# Ex_Controller_ExPwr.net
KiCad netlist of a schematic drawn in EAGLE
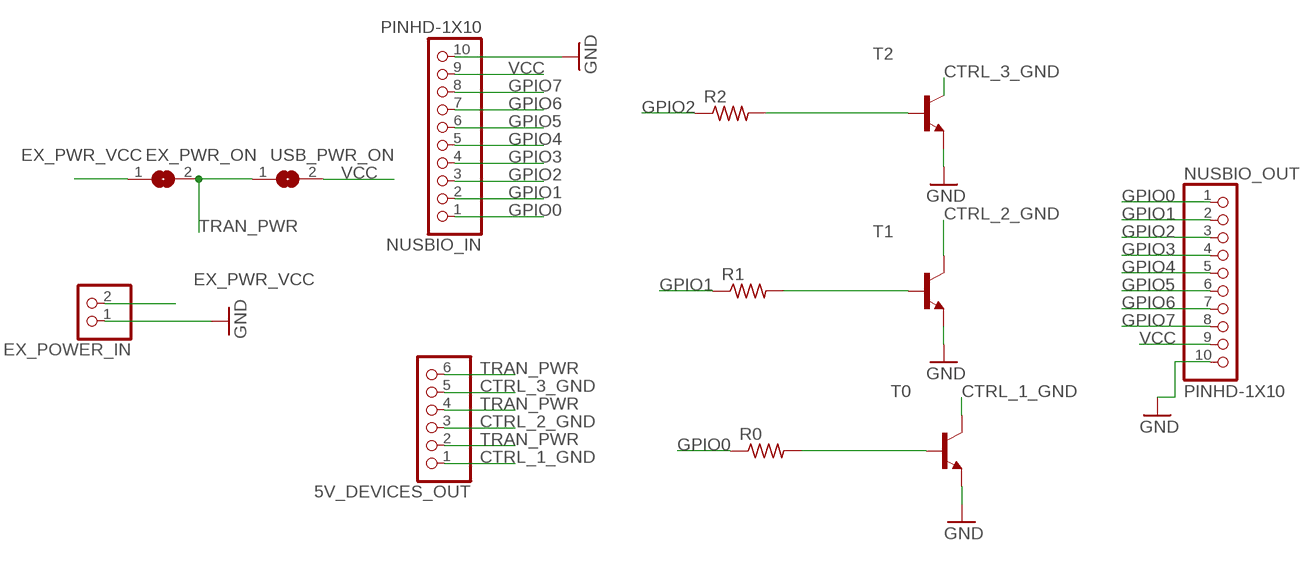
[diagram p0: schematic, sheet 1]

(export (version "E")
  (design (tool "Eeschema 10.0.6"))
  (components
    (comp (ref "5V_DEVICES_OUT")
      (value "PINHD-1X6")
      (footprint "eagle-import:1X06")
      (libsource (lib "eagle-import") (part "PINHD-1X6"))
    )
    (comp (ref "EX_POWER_IN")
      (value "PINHD-1X2")
      (footprint "eagle-import:1X02")
      (libsource (lib "eagle-import") (part "PINHD-1X2"))
    )
    (comp (ref "EX_PWR_ON")
      (value "SOLDERJUMPERREFLOW")
      (footprint "eagle-import:SOLDERJUMPER_REFLOW")
      (libsource (lib "eagle-import") (part "SOLDERJUMPERREFLOW"))
    )
    (comp (ref "NUSBIO_IN")
      (value "PINHD-1X10")
      (footprint "eagle-import:1X10-BIG")
      (libsource (lib "eagle-import") (part "PINHD-1X10"))
    )
    (comp (ref "NUSBIO_OUT")
      (value "PINHD-1X10")
      (footprint "eagle-import:1X10-BIG")
      (libsource (lib "eagle-import") (part "PINHD-1X10"))
    )
    (comp (ref "R0")
      (value "R-US_R0805")
      (footprint "eagle-import:R0805")
      (libsource (lib "eagle-import") (part "R-US_R0805"))
    )
    (comp (ref "R1")
      (value "R-US_R0805")
      (footprint "eagle-import:R0805")
      (libsource (lib "eagle-import") (part "R-US_R0805"))
    )
    (comp (ref "R2")
      (value "R-US_R0805")
      (footprint "eagle-import:R0805")
      (libsource (lib "eagle-import") (part "R-US_R0805"))
    )
    (comp (ref "T0")
      (value "MMBT3904LT1-NPN-SOT23-BEC")
      (footprint "eagle-import:SOT23-BEC")
      (libsource (lib "eagle-import") (part "-NPN-SOT23-BECMMBT3904LT1"))
    )
    (comp (ref "T1")
      (value "MMBT3904LT1-NPN-SOT23-BEC")
      (footprint "eagle-import:SOT23-BEC")
      (libsource (lib "eagle-import") (part "-NPN-SOT23-BECMMBT3904LT1"))
    )
    (comp (ref "T2")
      (value "MMBT3904LT1-NPN-SOT23-BEC")
      (footprint "eagle-import:SOT23-BEC")
      (libsource (lib "eagle-import") (part "-NPN-SOT23-BECMMBT3904LT1"))
    )
    (comp (ref "USB_PWR_ON")
      (value "SOLDERJUMPERREFLOW")
      (footprint "eagle-import:SOLDERJUMPER_REFLOW")
      (libsource (lib "eagle-import") (part "SOLDERJUMPERREFLOW"))
    )
  )
  (nets
    (net (code "1") (name "/CTRL_1_GND") (class "Default")
      (node (ref "5V_DEVICES_OUT") (pin "1") (pinfunction "1_1") (pintype "passive"))
      (node (ref "T0") (pin "C") (pinfunction "C_C") (pintype "passive"))
    )
    (net (code "2") (name "/CTRL_2_GND") (class "Default")
      (node (ref "5V_DEVICES_OUT") (pin "3") (pinfunction "3_3") (pintype "passive"))
      (node (ref "T1") (pin "C") (pinfunction "C_C") (pintype "passive"))
    )
    (net (code "3") (name "/CTRL_3_GND") (class "Default")
      (node (ref "5V_DEVICES_OUT") (pin "5") (pinfunction "5_5") (pintype "passive"))
      (node (ref "T2") (pin "C") (pinfunction "C_C") (pintype "passive"))
    )
    (net (code "4") (name "/EX_PWR_VCC") (class "Default")
      (node (ref "EX_POWER_IN") (pin "2") (pinfunction "2_2") (pintype "passive"))
      (node (ref "EX_PWR_ON") (pin "1") (pinfunction "1_1") (pintype "passive"))
    )
    (net (code "5") (name "/GPIO0") (class "Default")
      (node (ref "NUSBIO_IN") (pin "1") (pinfunction "1_1") (pintype "passive"))
      (node (ref "NUSBIO_OUT") (pin "1") (pinfunction "1_1") (pintype "passive"))
      (node (ref "R0") (pin "1") (pinfunction "1_1") (pintype "passive"))
    )
    (net (code "6") (name "/GPIO1") (class "Default")
      (node (ref "NUSBIO_IN") (pin "2") (pinfunction "2_2") (pintype "passive"))
      (node (ref "NUSBIO_OUT") (pin "2") (pinfunction "2_2") (pintype "passive"))
      (node (ref "R1") (pin "1") (pinfunction "1_1") (pintype "passive"))
    )
    (net (code "7") (name "/GPIO2") (class "Default")
      (node (ref "NUSBIO_IN") (pin "3") (pinfunction "3_3") (pintype "passive"))
      (node (ref "NUSBIO_OUT") (pin "3") (pinfunction "3_3") (pintype "passive"))
      (node (ref "R2") (pin "1") (pinfunction "1_1") (pintype "passive"))
    )
    (net (code "8") (name "/GPIO3") (class "Default")
      (node (ref "NUSBIO_IN") (pin "4") (pinfunction "4_4") (pintype "passive"))
      (node (ref "NUSBIO_OUT") (pin "4") (pinfunction "4_4") (pintype "passive"))
    )
    (net (code "9") (name "/GPIO4") (class "Default")
      (node (ref "NUSBIO_IN") (pin "5") (pinfunction "5_5") (pintype "passive"))
      (node (ref "NUSBIO_OUT") (pin "5") (pinfunction "5_5") (pintype "passive"))
    )
    (net (code "10") (name "/GPIO5") (class "Default")
      (node (ref "NUSBIO_IN") (pin "6") (pinfunction "6_6") (pintype "passive"))
      (node (ref "NUSBIO_OUT") (pin "6") (pinfunction "6_6") (pintype "passive"))
    )
    (net (code "11") (name "/GPIO6") (class "Default")
      (node (ref "NUSBIO_IN") (pin "7") (pinfunction "7_7") (pintype "passive"))
      (node (ref "NUSBIO_OUT") (pin "7") (pinfunction "7_7") (pintype "passive"))
    )
    (net (code "12") (name "/GPIO7") (class "Default")
      (node (ref "NUSBIO_IN") (pin "8") (pinfunction "8_8") (pintype "passive"))
      (node (ref "NUSBIO_OUT") (pin "8") (pinfunction "8_8") (pintype "passive"))
    )
    (net (code "13") (name "/TRAN_PWR") (class "Default")
      (node (ref "5V_DEVICES_OUT") (pin "2") (pinfunction "2_2") (pintype "passive"))
      (node (ref "5V_DEVICES_OUT") (pin "4") (pinfunction "4_4") (pintype "passive"))
      (node (ref "5V_DEVICES_OUT") (pin "6") (pinfunction "6_6") (pintype "passive"))
      (node (ref "EX_PWR_ON") (pin "2") (pinfunction "2_2") (pintype "passive"))
      (node (ref "USB_PWR_ON") (pin "1") (pinfunction "1_1") (pintype "passive"))
    )
    (net (code "14") (name "/VCC") (class "Default")
      (node (ref "NUSBIO_IN") (pin "9") (pinfunction "9_9") (pintype "passive"))
      (node (ref "NUSBIO_OUT") (pin "9") (pinfunction "9_9") (pintype "passive"))
      (node (ref "USB_PWR_ON") (pin "2") (pinfunction "2_2") (pintype "passive"))
    )
    (net (code "15") (name "GND") (class "Default")
      (node (ref "EX_POWER_IN") (pin "1") (pinfunction "1_1") (pintype "passive"))
      (node (ref "NUSBIO_IN") (pin "10") (pinfunction "10_10") (pintype "passive"))
      (node (ref "NUSBIO_OUT") (pin "10") (pinfunction "10_10") (pintype "passive"))
      (node (ref "T0") (pin "E") (pinfunction "E_E") (pintype "passive"))
      (node (ref "T1") (pin "E") (pinfunction "E_E") (pintype "passive"))
      (node (ref "T2") (pin "E") (pinfunction "E_E") (pintype "passive"))
    )
    (net (code "16") (name "Net-(R0-Pad2)") (class "Default")
      (node (ref "R0") (pin "2") (pinfunction "2_2") (pintype "passive"))
      (node (ref "T0") (pin "B") (pinfunction "B_B") (pintype "passive"))
    )
    (net (code "17") (name "Net-(R1-Pad2)") (class "Default")
      (node (ref "R1") (pin "2") (pinfunction "2_2") (pintype "passive"))
      (node (ref "T1") (pin "B") (pinfunction "B_B") (pintype "passive"))
    )
    (net (code "18") (name "Net-(R2-Pad2)") (class "Default")
      (node (ref "R2") (pin "2") (pinfunction "2_2") (pintype "passive"))
      (node (ref "T2") (pin "B") (pinfunction "B_B") (pintype "passive"))
    )
  )
)
